# basicbridge5v1A.net
KiCad netlist of a schematic drawn in EAGLE
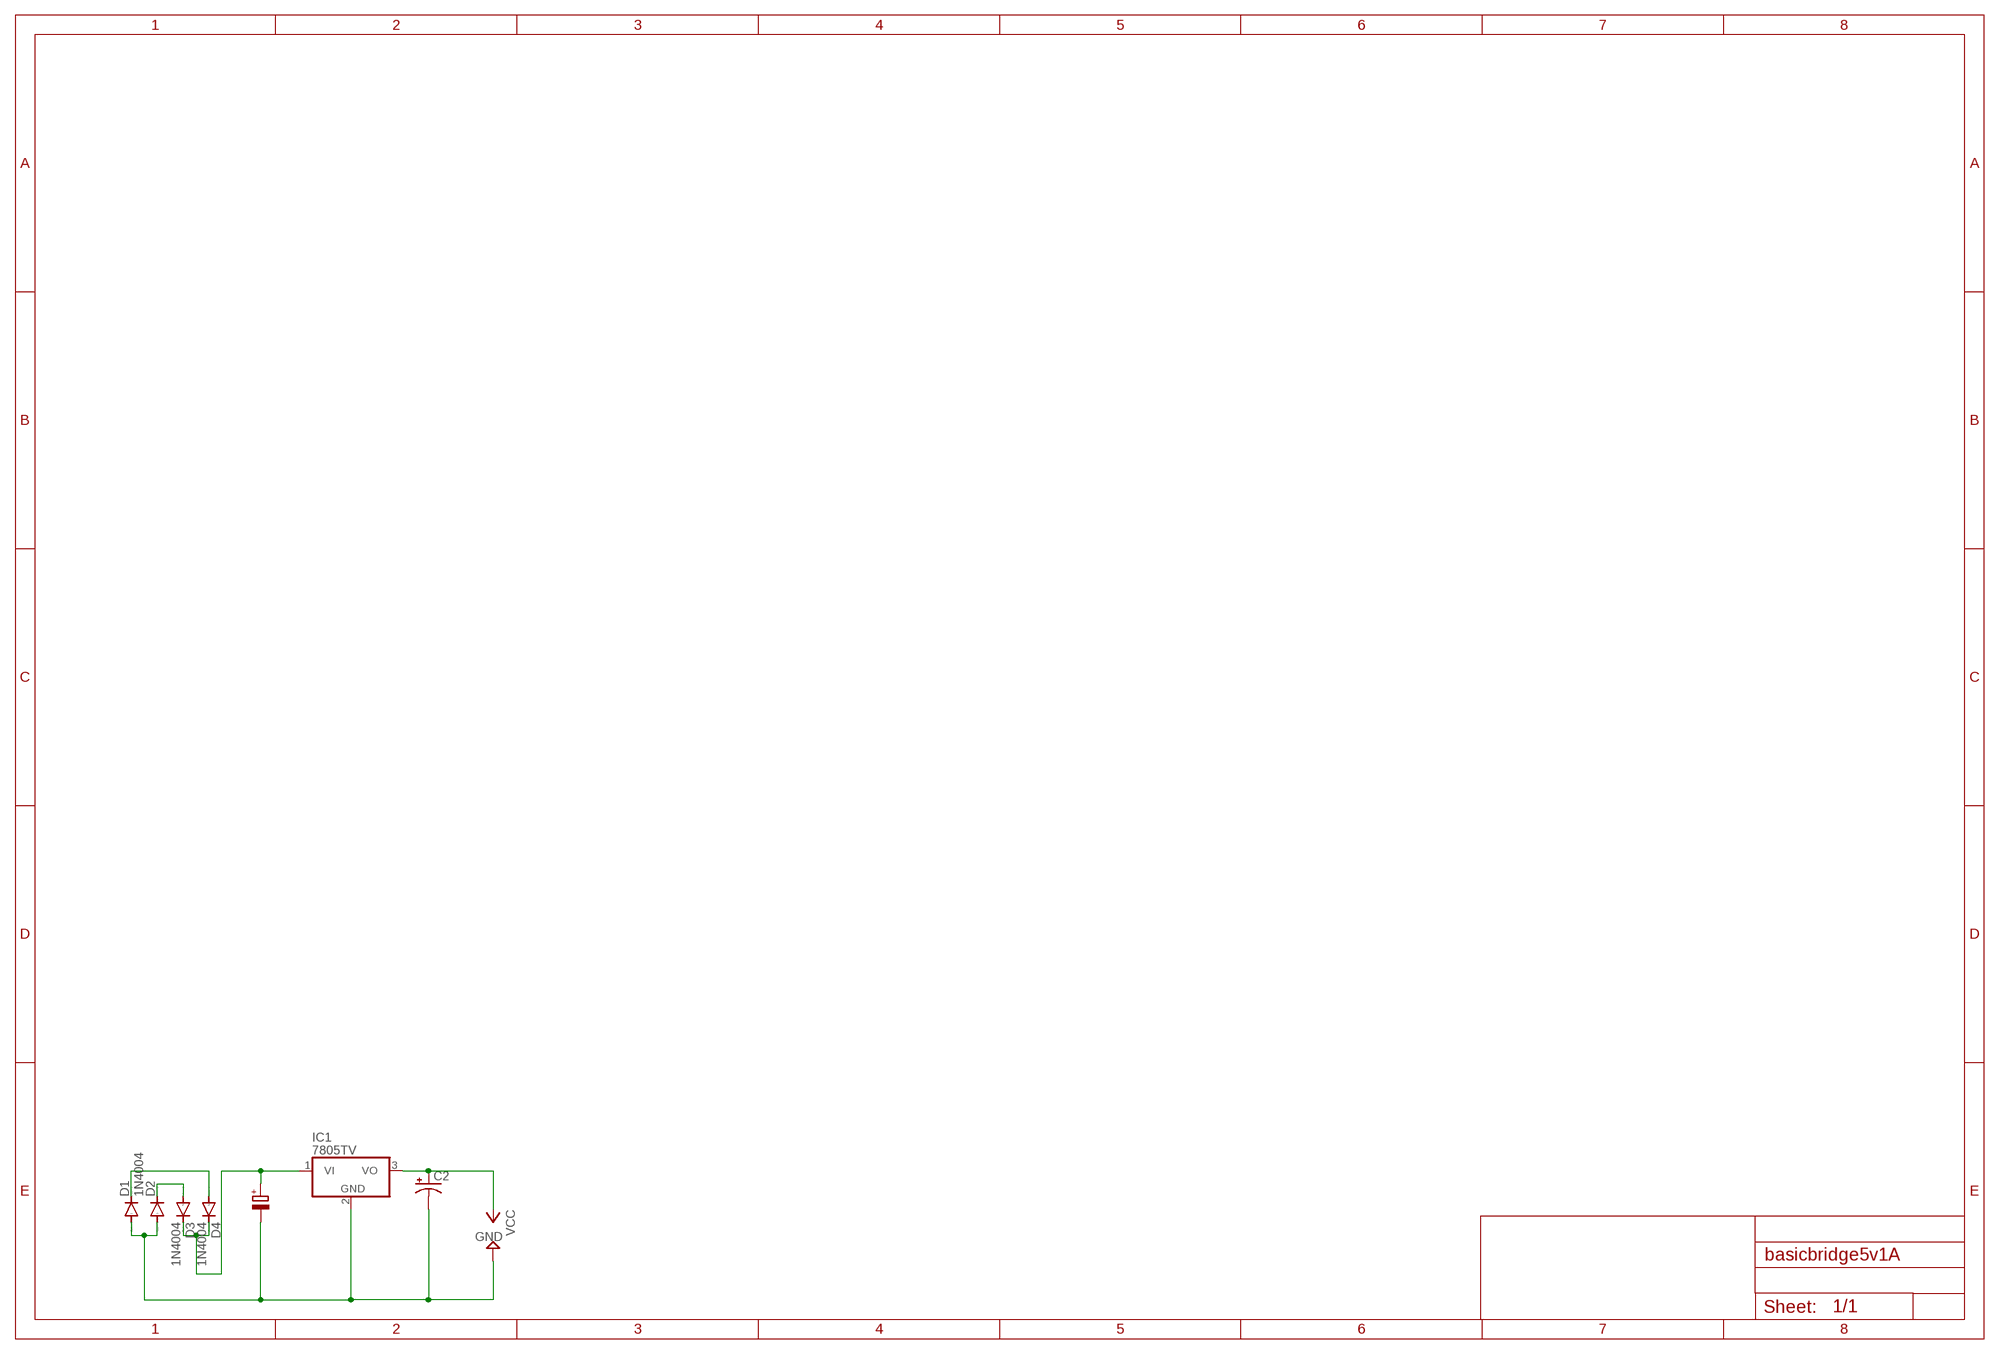
[diagram p0: schematic, sheet 1]

(export (version "E")
  (design (tool "Eeschema 10.0.6"))
  (components
    (comp (ref "C2")
      (value "CPOL-USE2.5-5V")
      (footprint "eagle-import:E2,5-4R")
      (libsource (lib "eagle-import") (part "CPOL-USE2.5-5V"))
    )
    (comp (ref "D1")
      (value "1N4004")
      (footprint "eagle-import:DO41-10")
      (libsource (lib "eagle-import") (part "1N4004"))
    )
    (comp (ref "D2")
      (value "1N4004")
      (footprint "eagle-import:DO41-10")
      (libsource (lib "eagle-import") (part "1N4004"))
    )
    (comp (ref "D3")
      (value "1N4004")
      (footprint "eagle-import:DO41-10")
      (libsource (lib "eagle-import") (part "1N4004"))
    )
    (comp (ref "D4")
      (value "1N4004")
      (footprint "eagle-import:DO41-10")
      (libsource (lib "eagle-import") (part "1N4004"))
    )
    (comp (ref "IC1")
      (value "7805TV")
      (footprint "eagle-import:TO220V")
      (libsource (lib "eagle-import") (part "78TV05"))
    )
  )
  (nets
    (net (code "1") (name "GND") (class "Default")
      (node (ref "C2") (pin "-") (pinfunction "-_-") (pintype "passive"))
      (node (ref "D1") (pin "A") (pinfunction "A_A") (pintype "passive"))
      (node (ref "D2") (pin "A") (pinfunction "A_A") (pintype "passive"))
      (node (ref "IC1") (pin "2") (pinfunction "GND_2") (pintype "passive"))
    )
    (net (code "2") (name "Net-(D1-PadC)") (class "Default")
      (node (ref "D1") (pin "C") (pinfunction "C_C") (pintype "passive"))
      (node (ref "D4") (pin "A") (pinfunction "A_A") (pintype "passive"))
    )
    (net (code "3") (name "Net-(D2-PadC)") (class "Default")
      (node (ref "D2") (pin "C") (pinfunction "C_C") (pintype "passive"))
      (node (ref "D3") (pin "A") (pinfunction "A_A") (pintype "passive"))
    )
    (net (code "4") (name "Net-(IC1-VI)") (class "Default")
      (node (ref "D3") (pin "C") (pinfunction "C_C") (pintype "passive"))
      (node (ref "D4") (pin "C") (pinfunction "C_C") (pintype "passive"))
      (node (ref "IC1") (pin "1") (pinfunction "VI_1") (pintype "input"))
    )
    (net (code "5") (name "VCC") (class "Default")
      (node (ref "C2") (pin "+") (pinfunction "+_+") (pintype "passive"))
      (node (ref "IC1") (pin "3") (pinfunction "VO_3") (pintype "passive"))
    )
  )
)
